# zmJackBoard.net
KiCad netlist of a schematic drawn in EAGLE
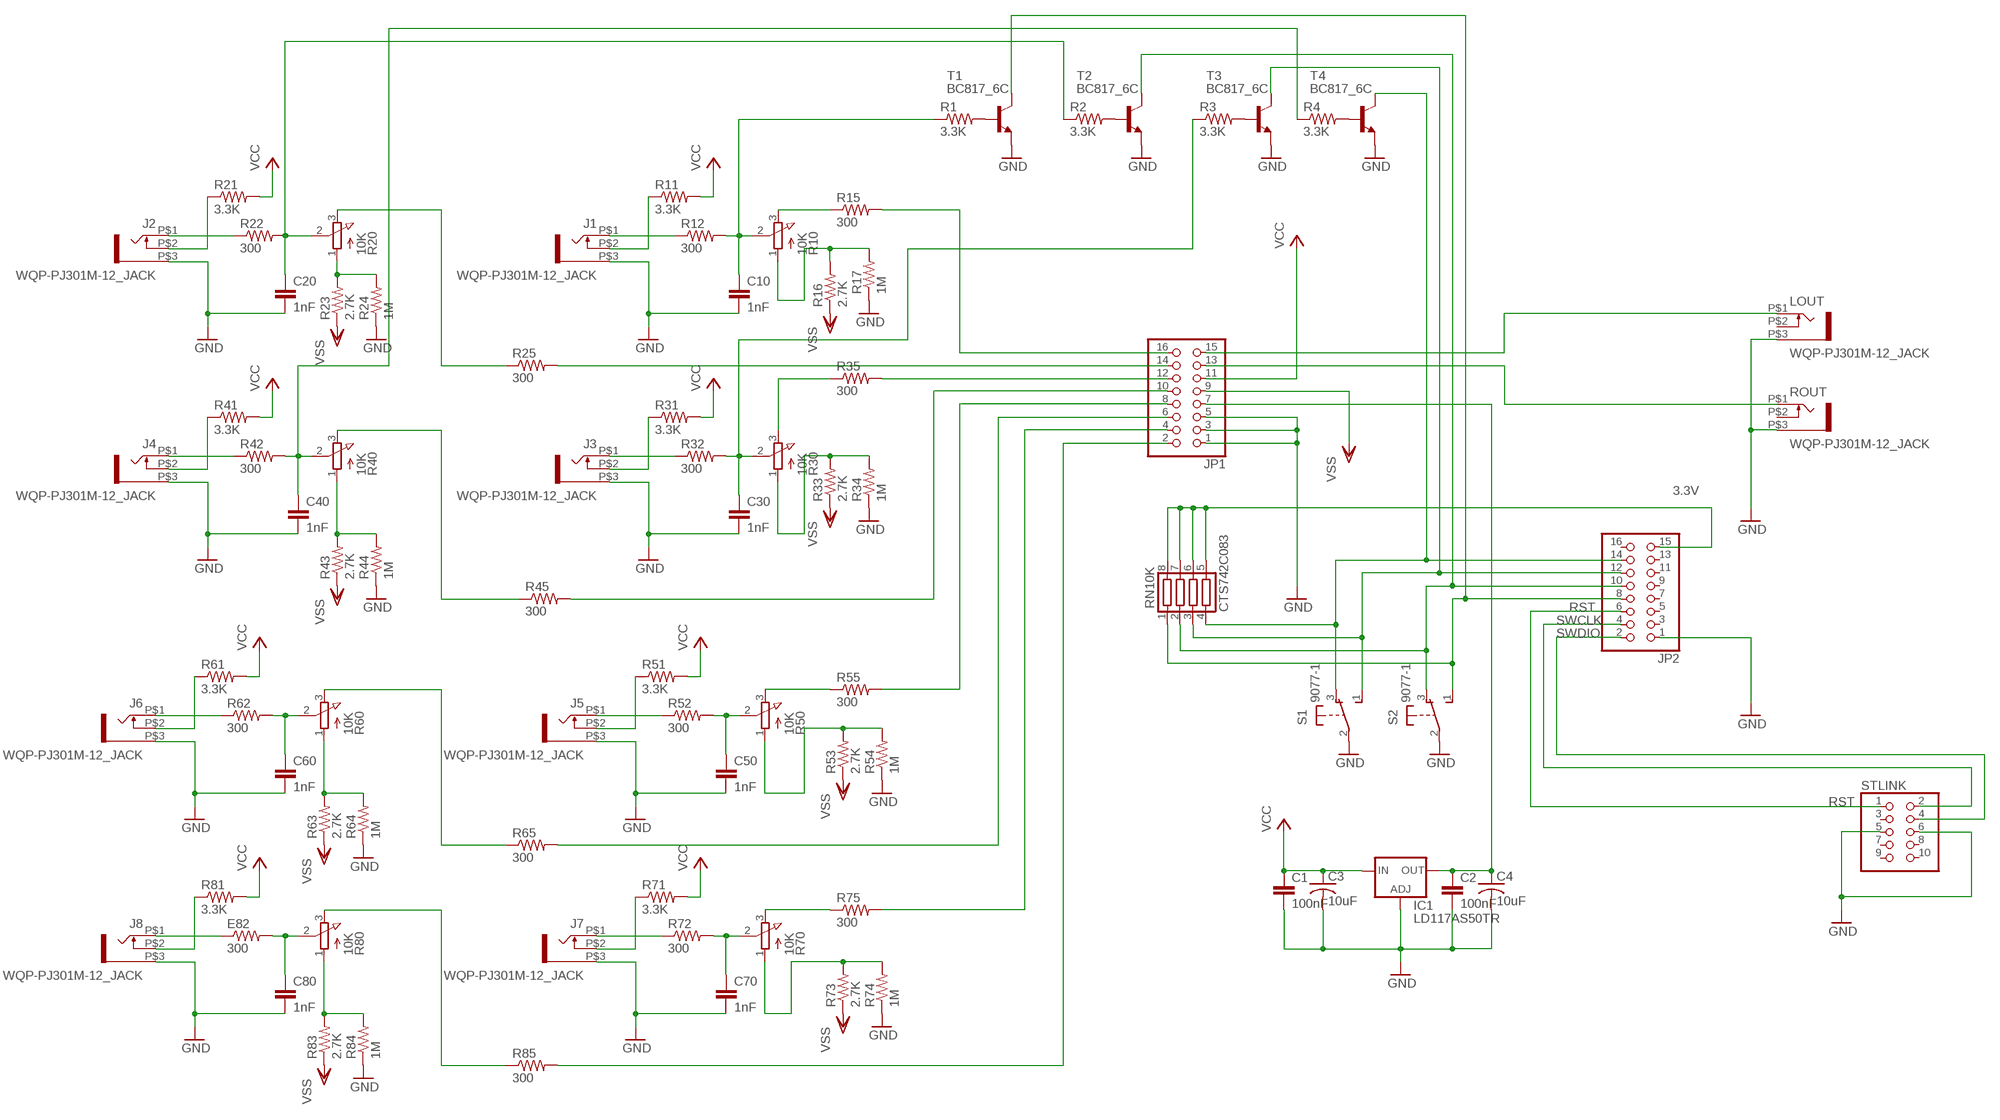
[diagram p0: schematic, sheet 1]

(export (version "E")
  (design (tool "Eeschema 10.0.6"))
  (components
    (comp (ref "C1")
      (value "100nF")
      (footprint "eagle-import:C0805")
      (libsource (lib "eagle-import") (part "C-EUC0805"))
    )
    (comp (ref "C2")
      (value "100nF")
      (footprint "eagle-import:C0805")
      (libsource (lib "eagle-import") (part "C-EUC0805"))
    )
    (comp (ref "C3")
      (value "10uF")
      (footprint "eagle-import:C1206")
      (libsource (lib "eagle-import") (part "C-USC1206"))
    )
    (comp (ref "C4")
      (value "10uF")
      (footprint "eagle-import:C1206")
      (libsource (lib "eagle-import") (part "C-USC1206"))
    )
    (comp (ref "C10")
      (value "1nF")
      (footprint "eagle-import:C0805")
      (libsource (lib "eagle-import") (part "C-EUC0805"))
    )
    (comp (ref "C20")
      (value "1nF")
      (footprint "eagle-import:C0805")
      (libsource (lib "eagle-import") (part "C-EUC0805"))
    )
    (comp (ref "C30")
      (value "1nF")
      (footprint "eagle-import:C0805")
      (libsource (lib "eagle-import") (part "C-EUC0805"))
    )
    (comp (ref "C40")
      (value "1nF")
      (footprint "eagle-import:C0805")
      (libsource (lib "eagle-import") (part "C-EUC0805"))
    )
    (comp (ref "C50")
      (value "1nF")
      (footprint "eagle-import:C0805")
      (libsource (lib "eagle-import") (part "C-EUC0805"))
    )
    (comp (ref "C60")
      (value "1nF")
      (footprint "eagle-import:C0805")
      (libsource (lib "eagle-import") (part "C-EUC0805"))
    )
    (comp (ref "C70")
      (value "1nF")
      (footprint "eagle-import:C0805")
      (libsource (lib "eagle-import") (part "C-EUC0805"))
    )
    (comp (ref "C80")
      (value "1nF")
      (footprint "eagle-import:C0805")
      (libsource (lib "eagle-import") (part "C-EUC0805"))
    )
    (comp (ref "E82")
      (value "300")
      (footprint "eagle-import:M0805")
      (libsource (lib "eagle-import") (part "R-US_M0805"))
    )
    (comp (ref "IC1")
      (value "LD117AS50TR")
      (footprint "eagle-import:SOT223")
      (libsource (lib "eagle-import") (part "LD117A?S50TR"))
    )
    (comp (ref "J1")
      (value "WQP-PJ301M-12_JACK")
      (footprint "eagle-import:WQP-PJ301M-12_JACK")
      (libsource (lib "eagle-import") (part "WQP-PJ301M-12_JACK"))
    )
    (comp (ref "J2")
      (value "WQP-PJ301M-12_JACK")
      (footprint "eagle-import:WQP-PJ301M-12_JACK")
      (libsource (lib "eagle-import") (part "WQP-PJ301M-12_JACK"))
    )
    (comp (ref "J3")
      (value "WQP-PJ301M-12_JACK")
      (footprint "eagle-import:WQP-PJ301M-12_JACK")
      (libsource (lib "eagle-import") (part "WQP-PJ301M-12_JACK"))
    )
    (comp (ref "J4")
      (value "WQP-PJ301M-12_JACK")
      (footprint "eagle-import:WQP-PJ301M-12_JACK")
      (libsource (lib "eagle-import") (part "WQP-PJ301M-12_JACK"))
    )
    (comp (ref "J5")
      (value "WQP-PJ301M-12_JACK")
      (footprint "eagle-import:WQP-PJ301M-12_JACK")
      (libsource (lib "eagle-import") (part "WQP-PJ301M-12_JACK"))
    )
    (comp (ref "J6")
      (value "WQP-PJ301M-12_JACK")
      (footprint "eagle-import:WQP-PJ301M-12_JACK")
      (libsource (lib "eagle-import") (part "WQP-PJ301M-12_JACK"))
    )
    (comp (ref "J7")
      (value "WQP-PJ301M-12_JACK")
      (footprint "eagle-import:WQP-PJ301M-12_JACK")
      (libsource (lib "eagle-import") (part "WQP-PJ301M-12_JACK"))
    )
    (comp (ref "J8")
      (value "WQP-PJ301M-12_JACK")
      (footprint "eagle-import:WQP-PJ301M-12_JACK")
      (libsource (lib "eagle-import") (part "WQP-PJ301M-12_JACK"))
    )
    (comp (ref "JP1")
      (value "PINHD-2X8")
      (footprint "eagle-import:2X08")
      (libsource (lib "eagle-import") (part "PINHD-2X8"))
    )
    (comp (ref "JP2")
      (value "PINHD-2X8")
      (footprint "eagle-import:2X08")
      (libsource (lib "eagle-import") (part "PINHD-2X8"))
    )
    (comp (ref "LOUT")
      (value "WQP-PJ301M-12_JACK")
      (footprint "eagle-import:WQP-PJ301M-12_JACK")
      (libsource (lib "eagle-import") (part "WQP-PJ301M-12_JACK"))
    )
    (comp (ref "R1")
      (value "3.3K")
      (footprint "eagle-import:M0805")
      (libsource (lib "eagle-import") (part "R-US_M0805"))
    )
    (comp (ref "R2")
      (value "3.3K")
      (footprint "eagle-import:M0805")
      (libsource (lib "eagle-import") (part "R-US_M0805"))
    )
    (comp (ref "R3")
      (value "3.3K")
      (footprint "eagle-import:M0805")
      (libsource (lib "eagle-import") (part "R-US_M0805"))
    )
    (comp (ref "R4")
      (value "3.3K")
      (footprint "eagle-import:M0805")
      (libsource (lib "eagle-import") (part "R-US_M0805"))
    )
    (comp (ref "R10")
      (value "10K")
      (footprint "eagle-import:EVUFXL")
      (libsource (lib "eagle-import") (part "EVULF3"))
    )
    (comp (ref "R11")
      (value "3.3K")
      (footprint "eagle-import:M0805")
      (libsource (lib "eagle-import") (part "R-US_M0805"))
    )
    (comp (ref "R12")
      (value "300")
      (footprint "eagle-import:M0805")
      (libsource (lib "eagle-import") (part "R-US_M0805"))
    )
    (comp (ref "R15")
      (value "300")
      (footprint "eagle-import:M0805")
      (libsource (lib "eagle-import") (part "R-US_M0805"))
    )
    (comp (ref "R16")
      (value "2.7K")
      (footprint "eagle-import:M0805")
      (libsource (lib "eagle-import") (part "R-US_M0805"))
    )
    (comp (ref "R17")
      (value "1M")
      (footprint "eagle-import:M0805")
      (libsource (lib "eagle-import") (part "R-US_M0805"))
    )
    (comp (ref "R20")
      (value "10K")
      (footprint "eagle-import:EVUFXL")
      (libsource (lib "eagle-import") (part "EVULF3"))
    )
    (comp (ref "R21")
      (value "3.3K")
      (footprint "eagle-import:M0805")
      (libsource (lib "eagle-import") (part "R-US_M0805"))
    )
    (comp (ref "R22")
      (value "300")
      (footprint "eagle-import:M0805")
      (libsource (lib "eagle-import") (part "R-US_M0805"))
    )
    (comp (ref "R23")
      (value "2.7K")
      (footprint "eagle-import:M0805")
      (libsource (lib "eagle-import") (part "R-US_M0805"))
    )
    (comp (ref "R24")
      (value "1M")
      (footprint "eagle-import:M0805")
      (libsource (lib "eagle-import") (part "R-US_M0805"))
    )
    (comp (ref "R25")
      (value "300")
      (footprint "eagle-import:M0805")
      (libsource (lib "eagle-import") (part "R-US_M0805"))
    )
    (comp (ref "R30")
      (value "10K")
      (footprint "eagle-import:EVUFXL")
      (libsource (lib "eagle-import") (part "EVULF3"))
    )
    (comp (ref "R31")
      (value "3.3K")
      (footprint "eagle-import:M0805")
      (libsource (lib "eagle-import") (part "R-US_M0805"))
    )
    (comp (ref "R32")
      (value "300")
      (footprint "eagle-import:M0805")
      (libsource (lib "eagle-import") (part "R-US_M0805"))
    )
    (comp (ref "R33")
      (value "2.7K")
      (footprint "eagle-import:M0805")
      (libsource (lib "eagle-import") (part "R-US_M0805"))
    )
    (comp (ref "R34")
      (value "1M")
      (footprint "eagle-import:M0805")
      (libsource (lib "eagle-import") (part "R-US_M0805"))
    )
    (comp (ref "R35")
      (value "300")
      (footprint "eagle-import:M0805")
      (libsource (lib "eagle-import") (part "R-US_M0805"))
    )
    (comp (ref "R40")
      (value "10K")
      (footprint "eagle-import:EVUFXL")
      (libsource (lib "eagle-import") (part "EVULF3"))
    )
    (comp (ref "R41")
      (value "3.3K")
      (footprint "eagle-import:M0805")
      (libsource (lib "eagle-import") (part "R-US_M0805"))
    )
    (comp (ref "R42")
      (value "300")
      (footprint "eagle-import:M0805")
      (libsource (lib "eagle-import") (part "R-US_M0805"))
    )
    (comp (ref "R43")
      (value "2.7K")
      (footprint "eagle-import:M0805")
      (libsource (lib "eagle-import") (part "R-US_M0805"))
    )
    (comp (ref "R44")
      (value "1M")
      (footprint "eagle-import:M0805")
      (libsource (lib "eagle-import") (part "R-US_M0805"))
    )
    (comp (ref "R45")
      (value "300")
      (footprint "eagle-import:M0805")
      (libsource (lib "eagle-import") (part "R-US_M0805"))
    )
    (comp (ref "R50")
      (value "10K")
      (footprint "eagle-import:EVUFXL")
      (libsource (lib "eagle-import") (part "EVULF3"))
    )
    (comp (ref "R51")
      (value "3.3K")
      (footprint "eagle-import:M0805")
      (libsource (lib "eagle-import") (part "R-US_M0805"))
    )
    (comp (ref "R52")
      (value "300")
      (footprint "eagle-import:M0805")
      (libsource (lib "eagle-import") (part "R-US_M0805"))
    )
    (comp (ref "R53")
      (value "2.7K")
      (footprint "eagle-import:M0805")
      (libsource (lib "eagle-import") (part "R-US_M0805"))
    )
    (comp (ref "R54")
      (value "1M")
      (footprint "eagle-import:M0805")
      (libsource (lib "eagle-import") (part "R-US_M0805"))
    )
    (comp (ref "R55")
      (value "300")
      (footprint "eagle-import:M0805")
      (libsource (lib "eagle-import") (part "R-US_M0805"))
    )
    (comp (ref "R60")
      (value "10K")
      (footprint "eagle-import:EVUFXL")
      (libsource (lib "eagle-import") (part "EVULF3"))
    )
    (comp (ref "R61")
      (value "3.3K")
      (footprint "eagle-import:M0805")
      (libsource (lib "eagle-import") (part "R-US_M0805"))
    )
    (comp (ref "R62")
      (value "300")
      (footprint "eagle-import:M0805")
      (libsource (lib "eagle-import") (part "R-US_M0805"))
    )
    (comp (ref "R63")
      (value "2.7K")
      (footprint "eagle-import:M0805")
      (libsource (lib "eagle-import") (part "R-US_M0805"))
    )
    (comp (ref "R64")
      (value "1M")
      (footprint "eagle-import:M0805")
      (libsource (lib "eagle-import") (part "R-US_M0805"))
    )
    (comp (ref "R65")
      (value "300")
      (footprint "eagle-import:M0805")
      (libsource (lib "eagle-import") (part "R-US_M0805"))
    )
    (comp (ref "R70")
      (value "10K")
      (footprint "eagle-import:EVUFXL")
      (libsource (lib "eagle-import") (part "EVULF3"))
    )
    (comp (ref "R71")
      (value "3.3K")
      (footprint "eagle-import:M0805")
      (libsource (lib "eagle-import") (part "R-US_M0805"))
    )
    (comp (ref "R72")
      (value "300")
      (footprint "eagle-import:M0805")
      (libsource (lib "eagle-import") (part "R-US_M0805"))
    )
    (comp (ref "R73")
      (value "2.7K")
      (footprint "eagle-import:M0805")
      (libsource (lib "eagle-import") (part "R-US_M0805"))
    )
    (comp (ref "R74")
      (value "1M")
      (footprint "eagle-import:M0805")
      (libsource (lib "eagle-import") (part "R-US_M0805"))
    )
    (comp (ref "R75")
      (value "300")
      (footprint "eagle-import:M0805")
      (libsource (lib "eagle-import") (part "R-US_M0805"))
    )
    (comp (ref "R80")
      (value "10K")
      (footprint "eagle-import:EVUFXL")
      (libsource (lib "eagle-import") (part "EVULF3"))
    )
    (comp (ref "R81")
      (value "3.3K")
      (footprint "eagle-import:M0805")
      (libsource (lib "eagle-import") (part "R-US_M0805"))
    )
    (comp (ref "R83")
      (value "2.7K")
      (footprint "eagle-import:M0805")
      (libsource (lib "eagle-import") (part "R-US_M0805"))
    )
    (comp (ref "R84")
      (value "1M")
      (footprint "eagle-import:M0805")
      (libsource (lib "eagle-import") (part "R-US_M0805"))
    )
    (comp (ref "R85")
      (value "300")
      (footprint "eagle-import:M0805")
      (libsource (lib "eagle-import") (part "R-US_M0805"))
    )
    (comp (ref "RN10K")
      (value "CTS742C083")
      (footprint "eagle-import:CTS742C083")
      (libsource (lib "eagle-import") (part "CTS742C083"))
    )
    (comp (ref "ROUT")
      (value "WQP-PJ301M-12_JACK")
      (footprint "eagle-import:WQP-PJ301M-12_JACK")
      (libsource (lib "eagle-import") (part "WQP-PJ301M-12_JACK"))
    )
    (comp (ref "S1")
      (value "9077-1")
      (footprint "eagle-import:9077-1")
      (libsource (lib "eagle-import") (part "9077-1"))
    )
    (comp (ref "S2")
      (value "9077-1")
      (footprint "eagle-import:9077-1")
      (libsource (lib "eagle-import") (part "9077-1"))
    )
    (comp (ref "STLINK")
      (value "PINHD-2X5")
      (footprint "eagle-import:2X05")
      (libsource (lib "eagle-import") (part "PINHD-2X5"))
    )
    (comp (ref "T1")
      (value "BC817_6C")
      (footprint "eagle-import:SOT23-EBC")
      (libsource (lib "eagle-import") (part "-NPN-SOT23-EBC"))
    )
    (comp (ref "T2")
      (value "BC817_6C")
      (footprint "eagle-import:SOT23-EBC")
      (libsource (lib "eagle-import") (part "-NPN-SOT23-EBC"))
    )
    (comp (ref "T3")
      (value "BC817_6C")
      (footprint "eagle-import:SOT23-EBC")
      (libsource (lib "eagle-import") (part "-NPN-SOT23-EBC"))
    )
    (comp (ref "T4")
      (value "BC817_6C")
      (footprint "eagle-import:SOT23-EBC")
      (libsource (lib "eagle-import") (part "-NPN-SOT23-EBC"))
    )
  )
  (nets
    (net (code "1") (name "/3.3V") (class "Default")
      (node (ref "JP2") (pin "15") (pinfunction "15_15") (pintype "passive"))
      (node (ref "RN10K") (pin "5") (pinfunction "5_5") (pintype "passive"))
      (node (ref "RN10K") (pin "6") (pinfunction "6_6") (pintype "passive"))
      (node (ref "RN10K") (pin "7") (pinfunction "7_7") (pintype "passive"))
      (node (ref "RN10K") (pin "8") (pinfunction "8_8") (pintype "passive"))
    )
    (net (code "2") (name "/RST") (class "Default")
      (node (ref "JP2") (pin "6") (pinfunction "6_6") (pintype "passive"))
      (node (ref "STLINK") (pin "1") (pinfunction "1_1") (pintype "passive"))
    )
    (net (code "3") (name "/SWCLK") (class "Default")
      (node (ref "JP2") (pin "4") (pinfunction "4_4") (pintype "passive"))
      (node (ref "STLINK") (pin "2") (pinfunction "2_2") (pintype "passive"))
    )
    (net (code "4") (name "/SWDIO") (class "Default")
      (node (ref "JP2") (pin "2") (pinfunction "2_2") (pintype "passive"))
      (node (ref "STLINK") (pin "4") (pinfunction "4_4") (pintype "passive"))
    )
    (net (code "5") (name "GND") (class "Default")
      (node (ref "C1") (pin "2") (pinfunction "2_2") (pintype "passive"))
      (node (ref "C10") (pin "2") (pinfunction "2_2") (pintype "passive"))
      (node (ref "C2") (pin "2") (pinfunction "2_2") (pintype "passive"))
      (node (ref "C20") (pin "2") (pinfunction "2_2") (pintype "passive"))
      (node (ref "C3") (pin "2") (pinfunction "2_2") (pintype "passive"))
      (node (ref "C30") (pin "2") (pinfunction "2_2") (pintype "passive"))
      (node (ref "C4") (pin "2") (pinfunction "2_2") (pintype "passive"))
      (node (ref "C40") (pin "2") (pinfunction "2_2") (pintype "passive"))
      (node (ref "C50") (pin "2") (pinfunction "2_2") (pintype "passive"))
      (node (ref "C60") (pin "2") (pinfunction "2_2") (pintype "passive"))
      (node (ref "C70") (pin "2") (pinfunction "2_2") (pintype "passive"))
      (node (ref "C80") (pin "2") (pinfunction "2_2") (pintype "passive"))
      (node (ref "IC1") (pin "1") (pinfunction "ADJ_1") (pintype "input"))
      (node (ref "J1") (pin "P$3") (pinfunction "1_P$3") (pintype "passive"))
      (node (ref "J2") (pin "P$3") (pinfunction "1_P$3") (pintype "passive"))
      (node (ref "J3") (pin "P$3") (pinfunction "1_P$3") (pintype "passive"))
      (node (ref "J4") (pin "P$3") (pinfunction "1_P$3") (pintype "passive"))
      (node (ref "J5") (pin "P$3") (pinfunction "1_P$3") (pintype "passive"))
      (node (ref "J6") (pin "P$3") (pinfunction "1_P$3") (pintype "passive"))
      (node (ref "J7") (pin "P$3") (pinfunction "1_P$3") (pintype "passive"))
      (node (ref "J8") (pin "P$3") (pinfunction "1_P$3") (pintype "passive"))
      (node (ref "JP1") (pin "1") (pinfunction "1_1") (pintype "passive"))
      (node (ref "JP1") (pin "3") (pinfunction "3_3") (pintype "passive"))
      (node (ref "JP1") (pin "5") (pinfunction "5_5") (pintype "passive"))
      (node (ref "JP2") (pin "1") (pinfunction "1_1") (pintype "passive"))
      (node (ref "LOUT") (pin "P$3") (pinfunction "1_P$3") (pintype "passive"))
      (node (ref "R17") (pin "1") (pinfunction "1_1") (pintype "passive"))
      (node (ref "R24") (pin "1") (pinfunction "1_1") (pintype "passive"))
      (node (ref "R34") (pin "1") (pinfunction "1_1") (pintype "passive"))
      (node (ref "R44") (pin "1") (pinfunction "1_1") (pintype "passive"))
      (node (ref "R54") (pin "1") (pinfunction "1_1") (pintype "passive"))
      (node (ref "R64") (pin "1") (pinfunction "1_1") (pintype "passive"))
      (node (ref "R74") (pin "1") (pinfunction "1_1") (pintype "passive"))
      (node (ref "R84") (pin "1") (pinfunction "1_1") (pintype "passive"))
      (node (ref "ROUT") (pin "P$3") (pinfunction "1_P$3") (pintype "passive"))
      (node (ref "S1") (pin "2") (pinfunction "P_2") (pintype "passive"))
      (node (ref "S2") (pin "2") (pinfunction "P_2") (pintype "passive"))
      (node (ref "STLINK") (pin "5") (pinfunction "5_5") (pintype "passive"))
      (node (ref "STLINK") (pin "6") (pinfunction "6_6") (pintype "passive"))
      (node (ref "T1") (pin "E") (pinfunction "E_E") (pintype "passive"))
      (node (ref "T2") (pin "E") (pinfunction "E_E") (pintype "passive"))
      (node (ref "T3") (pin "E") (pinfunction "E_E") (pintype "passive"))
      (node (ref "T4") (pin "E") (pinfunction "E_E") (pintype "passive"))
    )
    (net (code "6") (name "Net-(IC1-OUT)") (class "Default")
      (node (ref "C2") (pin "1") (pinfunction "1_1") (pintype "passive"))
      (node (ref "C4") (pin "1") (pinfunction "1_1") (pintype "passive"))
      (node (ref "IC1") (pin "4") (pinfunction "OUT_4") (pintype "passive"))
      (node (ref "JP1") (pin "7") (pinfunction "7_7") (pintype "passive"))
    )
    (net (code "7") (name "Net-(J1-2)") (class "Default")
      (node (ref "J1") (pin "P$1") (pinfunction "2_P$1") (pintype "passive"))
      (node (ref "R12") (pin "1") (pinfunction "1_1") (pintype "passive"))
    )
    (net (code "8") (name "Net-(J1-3)") (class "Default")
      (node (ref "J1") (pin "P$2") (pinfunction "3_P$2") (pintype "passive"))
      (node (ref "R11") (pin "1") (pinfunction "1_1") (pintype "passive"))
    )
    (net (code "9") (name "Net-(J2-2)") (class "Default")
      (node (ref "J2") (pin "P$1") (pinfunction "2_P$1") (pintype "passive"))
      (node (ref "R22") (pin "1") (pinfunction "1_1") (pintype "passive"))
    )
    (net (code "10") (name "Net-(J2-3)") (class "Default")
      (node (ref "J2") (pin "P$2") (pinfunction "3_P$2") (pintype "passive"))
      (node (ref "R21") (pin "1") (pinfunction "1_1") (pintype "passive"))
    )
    (net (code "11") (name "Net-(J3-2)") (class "Default")
      (node (ref "J3") (pin "P$1") (pinfunction "2_P$1") (pintype "passive"))
      (node (ref "R32") (pin "1") (pinfunction "1_1") (pintype "passive"))
    )
    (net (code "12") (name "Net-(J3-3)") (class "Default")
      (node (ref "J3") (pin "P$2") (pinfunction "3_P$2") (pintype "passive"))
      (node (ref "R31") (pin "1") (pinfunction "1_1") (pintype "passive"))
    )
    (net (code "13") (name "Net-(J4-2)") (class "Default")
      (node (ref "J4") (pin "P$1") (pinfunction "2_P$1") (pintype "passive"))
      (node (ref "R42") (pin "1") (pinfunction "1_1") (pintype "passive"))
    )
    (net (code "14") (name "Net-(J4-3)") (class "Default")
      (node (ref "J4") (pin "P$2") (pinfunction "3_P$2") (pintype "passive"))
      (node (ref "R41") (pin "1") (pinfunction "1_1") (pintype "passive"))
    )
    (net (code "15") (name "Net-(J5-2)") (class "Default")
      (node (ref "J5") (pin "P$1") (pinfunction "2_P$1") (pintype "passive"))
      (node (ref "R52") (pin "1") (pinfunction "1_1") (pintype "passive"))
    )
    (net (code "16") (name "Net-(J5-3)") (class "Default")
      (node (ref "J5") (pin "P$2") (pinfunction "3_P$2") (pintype "passive"))
      (node (ref "R51") (pin "1") (pinfunction "1_1") (pintype "passive"))
    )
    (net (code "17") (name "Net-(J6-2)") (class "Default")
      (node (ref "J6") (pin "P$1") (pinfunction "2_P$1") (pintype "passive"))
      (node (ref "R62") (pin "1") (pinfunction "1_1") (pintype "passive"))
    )
    (net (code "18") (name "Net-(J6-3)") (class "Default")
      (node (ref "J6") (pin "P$2") (pinfunction "3_P$2") (pintype "passive"))
      (node (ref "R61") (pin "1") (pinfunction "1_1") (pintype "passive"))
    )
    (net (code "19") (name "Net-(J7-2)") (class "Default")
      (node (ref "J7") (pin "P$1") (pinfunction "2_P$1") (pintype "passive"))
      (node (ref "R72") (pin "1") (pinfunction "1_1") (pintype "passive"))
    )
    (net (code "20") (name "Net-(J7-3)") (class "Default")
      (node (ref "J7") (pin "P$2") (pinfunction "3_P$2") (pintype "passive"))
      (node (ref "R71") (pin "1") (pinfunction "1_1") (pintype "passive"))
    )
    (net (code "21") (name "Net-(J8-2)") (class "Default")
      (node (ref "E82") (pin "1") (pinfunction "1_1") (pintype "passive"))
      (node (ref "J8") (pin "P$1") (pinfunction "2_P$1") (pintype "passive"))
    )
    (net (code "22") (name "Net-(J8-3)") (class "Default")
      (node (ref "J8") (pin "P$2") (pinfunction "3_P$2") (pintype "passive"))
      (node (ref "R81") (pin "1") (pinfunction "1_1") (pintype "passive"))
    )
    (net (code "23") (name "Net-(JP1-Pad2)") (class "Default")
      (node (ref "JP1") (pin "2") (pinfunction "2_2") (pintype "passive"))
      (node (ref "R85") (pin "2") (pinfunction "2_2") (pintype "passive"))
    )
    (net (code "24") (name "Net-(JP1-Pad4)") (class "Default")
      (node (ref "JP1") (pin "4") (pinfunction "4_4") (pintype "passive"))
      (node (ref "R75") (pin "2") (pinfunction "2_2") (pintype "passive"))
    )
    (net (code "25") (name "Net-(JP1-Pad6)") (class "Default")
      (node (ref "JP1") (pin "6") (pinfunction "6_6") (pintype "passive"))
      (node (ref "R65") (pin "2") (pinfunction "2_2") (pintype "passive"))
    )
    (net (code "26") (name "Net-(JP1-Pad8)") (class "Default")
      (node (ref "JP1") (pin "8") (pinfunction "8_8") (pintype "passive"))
      (node (ref "R55") (pin "2") (pinfunction "2_2") (pintype "passive"))
    )
    (net (code "27") (name "Net-(JP1-Pad10)") (class "Default")
      (node (ref "JP1") (pin "10") (pinfunction "10_10") (pintype "passive"))
      (node (ref "R45") (pin "2") (pinfunction "2_2") (pintype "passive"))
    )
    (net (code "28") (name "Net-(JP1-Pad12)") (class "Default")
      (node (ref "JP1") (pin "12") (pinfunction "12_12") (pintype "passive"))
      (node (ref "R35") (pin "2") (pinfunction "2_2") (pintype "passive"))
    )
    (net (code "29") (name "Net-(JP1-Pad14)") (class "Default")
      (node (ref "JP1") (pin "14") (pinfunction "14_14") (pintype "passive"))
      (node (ref "R25") (pin "2") (pinfunction "2_2") (pintype "passive"))
    )
    (net (code "30") (name "Net-(JP1-Pad16)") (class "Default")
      (node (ref "JP1") (pin "16") (pinfunction "16_16") (pintype "passive"))
      (node (ref "R15") (pin "2") (pinfunction "2_2") (pintype "passive"))
    )
    (net (code "31") (name "Net-(LOUT-2)") (class "Default")
      (node (ref "JP1") (pin "15") (pinfunction "15_15") (pintype "passive"))
      (node (ref "LOUT") (pin "P$1") (pinfunction "2_P$1") (pintype "passive"))
    )
    (net (code "32") (name "Net-(R1-Pad2)") (class "Default")
      (node (ref "R1") (pin "2") (pinfunction "2_2") (pintype "passive"))
      (node (ref "T1") (pin "B") (pinfunction "B_B") (pintype "passive"))
    )
    (net (code "33") (name "Net-(R2-Pad2)") (class "Default")
      (node (ref "R2") (pin "2") (pinfunction "2_2") (pintype "passive"))
      (node (ref "T2") (pin "B") (pinfunction "B_B") (pintype "passive"))
    )
    (net (code "34") (name "Net-(R3-Pad2)") (class "Default")
      (node (ref "R3") (pin "2") (pinfunction "2_2") (pintype "passive"))
      (node (ref "T3") (pin "B") (pinfunction "B_B") (pintype "passive"))
    )
    (net (code "35") (name "Net-(R4-Pad2)") (class "Default")
      (node (ref "R4") (pin "2") (pinfunction "2_2") (pintype "passive"))
      (node (ref "T4") (pin "B") (pinfunction "B_B") (pintype "passive"))
    )
    (net (code "36") (name "Net-(R10-A)") (class "Default")
      (node (ref "R10") (pin "1") (pinfunction "A_1") (pintype "passive"))
      (node (ref "R16") (pin "2") (pinfunction "2_2") (pintype "passive"))
      (node (ref "R17") (pin "2") (pinfunction "2_2") (pintype "passive"))
    )
    (net (code "37") (name "Net-(R10-E)") (class "Default")
      (node (ref "R10") (pin "3") (pinfunction "E_3") (pintype "passive"))
      (node (ref "R15") (pin "1") (pinfunction "1_1") (pintype "passive"))
    )
    (net (code "38") (name "Net-(R10-S)") (class "Default")
      (node (ref "C10") (pin "1") (pinfunction "1_1") (pintype "passive"))
      (node (ref "R1") (pin "1") (pinfunction "1_1") (pintype "passive"))
      (node (ref "R10") (pin "2") (pinfunction "S_2") (pintype "passive"))
      (node (ref "R12") (pin "2") (pinfunction "2_2") (pintype "passive"))
    )
    (net (code "39") (name "Net-(R20-A)") (class "Default")
      (node (ref "R20") (pin "1") (pinfunction "A_1") (pintype "passive"))
      (node (ref "R23") (pin "2") (pinfunction "2_2") (pintype "passive"))
      (node (ref "R24") (pin "2") (pinfunction "2_2") (pintype "passive"))
    )
    (net (code "40") (name "Net-(R20-E)") (class "Default")
      (node (ref "R20") (pin "3") (pinfunction "E_3") (pintype "passive"))
      (node (ref "R25") (pin "1") (pinfunction "1_1") (pintype "passive"))
    )
    (net (code "41") (name "Net-(R20-S)") (class "Default")
      (node (ref "C20") (pin "1") (pinfunction "1_1") (pintype "passive"))
      (node (ref "R2") (pin "1") (pinfunction "1_1") (pintype "passive"))
      (node (ref "R20") (pin "2") (pinfunction "S_2") (pintype "passive"))
      (node (ref "R22") (pin "2") (pinfunction "2_2") (pintype "passive"))
    )
    (net (code "42") (name "Net-(R30-A)") (class "Default")
      (node (ref "R30") (pin "1") (pinfunction "A_1") (pintype "passive"))
      (node (ref "R33") (pin "2") (pinfunction "2_2") (pintype "passive"))
      (node (ref "R34") (pin "2") (pinfunction "2_2") (pintype "passive"))
    )
    (net (code "43") (name "Net-(R30-E)") (class "Default")
      (node (ref "R30") (pin "3") (pinfunction "E_3") (pintype "passive"))
      (node (ref "R35") (pin "1") (pinfunction "1_1") (pintype "passive"))
    )
    (net (code "44") (name "Net-(R30-S)") (class "Default")
      (node (ref "C30") (pin "1") (pinfunction "1_1") (pintype "passive"))
      (node (ref "R3") (pin "1") (pinfunction "1_1") (pintype "passive"))
      (node (ref "R30") (pin "2") (pinfunction "S_2") (pintype "passive"))
      (node (ref "R32") (pin "2") (pinfunction "2_2") (pintype "passive"))
    )
    (net (code "45") (name "Net-(R40-A)") (class "Default")
      (node (ref "R40") (pin "1") (pinfunction "A_1") (pintype "passive"))
      (node (ref "R43") (pin "2") (pinfunction "2_2") (pintype "passive"))
      (node (ref "R44") (pin "2") (pinfunction "2_2") (pintype "passive"))
    )
    (net (code "46") (name "Net-(R40-E)") (class "Default")
      (node (ref "R40") (pin "3") (pinfunction "E_3") (pintype "passive"))
      (node (ref "R45") (pin "1") (pinfunction "1_1") (pintype "passive"))
    )
    (net (code "47") (name "Net-(R40-S)") (class "Default")
      (node (ref "C40") (pin "1") (pinfunction "1_1") (pintype "passive"))
      (node (ref "R4") (pin "1") (pinfunction "1_1") (pintype "passive"))
      (node (ref "R40") (pin "2") (pinfunction "S_2") (pintype "passive"))
      (node (ref "R42") (pin "2") (pinfunction "2_2") (pintype "passive"))
    )
    (net (code "48") (name "Net-(R50-A)") (class "Default")
      (node (ref "R50") (pin "1") (pinfunction "A_1") (pintype "passive"))
      (node (ref "R53") (pin "2") (pinfunction "2_2") (pintype "passive"))
      (node (ref "R54") (pin "2") (pinfunction "2_2") (pintype "passive"))
    )
    (net (code "49") (name "Net-(R50-E)") (class "Default")
      (node (ref "R50") (pin "3") (pinfunction "E_3") (pintype "passive"))
      (node (ref "R55") (pin "1") (pinfunction "1_1") (pintype "passive"))
    )
    (net (code "50") (name "Net-(R50-S)") (class "Default")
      (node (ref "C50") (pin "1") (pinfunction "1_1") (pintype "passive"))
      (node (ref "R50") (pin "2") (pinfunction "S_2") (pintype "passive"))
      (node (ref "R52") (pin "2") (pinfunction "2_2") (pintype "passive"))
    )
    (net (code "51") (name "Net-(R60-A)") (class "Default")
      (node (ref "R60") (pin "1") (pinfunction "A_1") (pintype "passive"))
      (node (ref "R63") (pin "2") (pinfunction "2_2") (pintype "passive"))
      (node (ref "R64") (pin "2") (pinfunction "2_2") (pintype "passive"))
    )
    (net (code "52") (name "Net-(R60-E)") (class "Default")
      (node (ref "R60") (pin "3") (pinfunction "E_3") (pintype "passive"))
      (node (ref "R65") (pin "1") (pinfunction "1_1") (pintype "passive"))
    )
    (net (code "53") (name "Net-(R60-S)") (class "Default")
      (node (ref "C60") (pin "1") (pinfunction "1_1") (pintype "passive"))
      (node (ref "R60") (pin "2") (pinfunction "S_2") (pintype "passive"))
      (node (ref "R62") (pin "2") (pinfunction "2_2") (pintype "passive"))
    )
    (net (code "54") (name "Net-(R70-A)") (class "Default")
      (node (ref "R70") (pin "1") (pinfunction "A_1") (pintype "passive"))
      (node (ref "R73") (pin "2") (pinfunction "2_2") (pintype "passive"))
      (node (ref "R74") (pin "2") (pinfunction "2_2") (pintype "passive"))
    )
    (net (code "55") (name "Net-(R70-E)") (class "Default")
      (node (ref "R70") (pin "3") (pinfunction "E_3") (pintype "passive"))
      (node (ref "R75") (pin "1") (pinfunction "1_1") (pintype "passive"))
    )
    (net (code "56") (name "Net-(R70-S)") (class "Default")
      (node (ref "C70") (pin "1") (pinfunction "1_1") (pintype "passive"))
      (node (ref "R70") (pin "2") (pinfunction "S_2") (pintype "passive"))
      (node (ref "R72") (pin "2") (pinfunction "2_2") (pintype "passive"))
    )
    (net (code "57") (name "Net-(R80-A)") (class "Default")
      (node (ref "R80") (pin "1") (pinfunction "A_1") (pintype "passive"))
      (node (ref "R83") (pin "2") (pinfunction "2_2") (pintype "passive"))
      (node (ref "R84") (pin "2") (pinfunction "2_2") (pintype "passive"))
    )
    (net (code "58") (name "Net-(R80-E)") (class "Default")
      (node (ref "R80") (pin "3") (pinfunction "E_3") (pintype "passive"))
      (node (ref "R85") (pin "1") (pinfunction "1_1") (pintype "passive"))
    )
    (net (code "59") (name "Net-(R80-S)") (class "Default")
      (node (ref "C80") (pin "1") (pinfunction "1_1") (pintype "passive"))
      (node (ref "E82") (pin "2") (pinfunction "2_2") (pintype "passive"))
      (node (ref "R80") (pin "2") (pinfunction "S_2") (pintype "passive"))
    )
    (net (code "60") (name "Net-(ROUT-2)") (class "Default")
      (node (ref "JP1") (pin "13") (pinfunction "13_13") (pintype "passive"))
      (node (ref "ROUT") (pin "P$1") (pinfunction "2_P$1") (pintype "passive"))
    )
    (net (code "61") (name "Net-(S1-O)") (class "Default")
      (node (ref "JP2") (pin "14") (pinfunction "14_14") (pintype "passive"))
      (node (ref "RN10K") (pin "4") (pinfunction "4_4") (pintype "passive"))
      (node (ref "S1") (pin "3") (pinfunction "O_3") (pintype "passive"))
      (node (ref "T4") (pin "C") (pinfunction "C_C") (pintype "passive"))
    )
    (net (code "62") (name "Net-(S1-S)") (class "Default")
      (node (ref "JP2") (pin "12") (pinfunction "12_12") (pintype "passive"))
      (node (ref "RN10K") (pin "3") (pinfunction "3_3") (pintype "passive"))
      (node (ref "S1") (pin "1") (pinfunction "S_1") (pintype "passive"))
      (node (ref "T3") (pin "C") (pinfunction "C_C") (pintype "passive"))
    )
    (net (code "63") (name "Net-(S2-O)") (class "Default")
      (node (ref "JP2") (pin "10") (pinfunction "10_10") (pintype "passive"))
      (node (ref "RN10K") (pin "2") (pinfunction "2_2") (pintype "passive"))
      (node (ref "S2") (pin "3") (pinfunction "O_3") (pintype "passive"))
      (node (ref "T2") (pin "C") (pinfunction "C_C") (pintype "passive"))
    )
    (net (code "64") (name "Net-(S2-S)") (class "Default")
      (node (ref "JP2") (pin "8") (pinfunction "8_8") (pintype "passive"))
      (node (ref "RN10K") (pin "1") (pinfunction "1_1") (pintype "passive"))
      (node (ref "S2") (pin "1") (pinfunction "S_1") (pintype "passive"))
      (node (ref "T1") (pin "C") (pinfunction "C_C") (pintype "passive"))
    )
    (net (code "65") (name "VCC") (class "Default")
      (node (ref "C1") (pin "1") (pinfunction "1_1") (pintype "passive"))
      (node (ref "C3") (pin "1") (pinfunction "1_1") (pintype "passive"))
      (node (ref "IC1") (pin "3") (pinfunction "IN_3") (pintype "input"))
      (node (ref "JP1") (pin "11") (pinfunction "11_11") (pintype "passive"))
      (node (ref "R11") (pin "2") (pinfunction "2_2") (pintype "passive"))
      (node (ref "R21") (pin "2") (pinfunction "2_2") (pintype "passive"))
      (node (ref "R31") (pin "2") (pinfunction "2_2") (pintype "passive"))
      (node (ref "R41") (pin "2") (pinfunction "2_2") (pintype "passive"))
      (node (ref "R51") (pin "2") (pinfunction "2_2") (pintype "passive"))
      (node (ref "R61") (pin "2") (pinfunction "2_2") (pintype "passive"))
      (node (ref "R71") (pin "2") (pinfunction "2_2") (pintype "passive"))
      (node (ref "R81") (pin "2") (pinfunction "2_2") (pintype "passive"))
    )
    (net (code "66") (name "VSS") (class "Default")
      (node (ref "JP1") (pin "9") (pinfunction "9_9") (pintype "passive"))
      (node (ref "R16") (pin "1") (pinfunction "1_1") (pintype "passive"))
      (node (ref "R23") (pin "1") (pinfunction "1_1") (pintype "passive"))
      (node (ref "R33") (pin "1") (pinfunction "1_1") (pintype "passive"))
      (node (ref "R43") (pin "1") (pinfunction "1_1") (pintype "passive"))
      (node (ref "R53") (pin "1") (pinfunction "1_1") (pintype "passive"))
      (node (ref "R63") (pin "1") (pinfunction "1_1") (pintype "passive"))
      (node (ref "R73") (pin "1") (pinfunction "1_1") (pintype "passive"))
      (node (ref "R83") (pin "1") (pinfunction "1_1") (pintype "passive"))
    )
    (net (code "67") (name "unconnected-(JP2-Pad3)") (class "Default")
      (node (ref "JP2") (pin "3") (pinfunction "3_3") (pintype "passive"))
    )
    (net (code "68") (name "unconnected-(JP2-Pad5)") (class "Default")
      (node (ref "JP2") (pin "5") (pinfunction "5_5") (pintype "passive"))
    )
    (net (code "69") (name "unconnected-(JP2-Pad7)") (class "Default")
      (node (ref "JP2") (pin "7") (pinfunction "7_7") (pintype "passive"))
    )
    (net (code "70") (name "unconnected-(JP2-Pad9)") (class "Default")
      (node (ref "JP2") (pin "9") (pinfunction "9_9") (pintype "passive"))
    )
    (net (code "71") (name "unconnected-(JP2-Pad11)") (class "Default")
      (node (ref "JP2") (pin "11") (pinfunction "11_11") (pintype "passive"))
    )
    (net (code "72") (name "unconnected-(JP2-Pad13)") (class "Default")
      (node (ref "JP2") (pin "13") (pinfunction "13_13") (pintype "passive"))
    )
    (net (code "73") (name "unconnected-(JP2-Pad16)") (class "Default")
      (node (ref "JP2") (pin "16") (pinfunction "16_16") (pintype "passive"))
    )
    (net (code "74") (name "unconnected-(LOUT-3-PadP$2)") (class "Default")
      (node (ref "LOUT") (pin "P$2") (pinfunction "3_P$2") (pintype "passive"))
    )
    (net (code "75") (name "unconnected-(ROUT-3-PadP$2)") (class "Default")
      (node (ref "ROUT") (pin "P$2") (pinfunction "3_P$2") (pintype "passive"))
    )
    (net (code "76") (name "unconnected-(STLINK-Pad3)") (class "Default")
      (node (ref "STLINK") (pin "3") (pinfunction "3_3") (pintype "passive"))
    )
    (net (code "77") (name "unconnected-(STLINK-Pad7)") (class "Default")
      (node (ref "STLINK") (pin "7") (pinfunction "7_7") (pintype "passive"))
    )
    (net (code "78") (name "unconnected-(STLINK-Pad8)") (class "Default")
      (node (ref "STLINK") (pin "8") (pinfunction "8_8") (pintype "passive"))
    )
    (net (code "79") (name "unconnected-(STLINK-Pad9)") (class "Default")
      (node (ref "STLINK") (pin "9") (pinfunction "9_9") (pintype "passive"))
    )
    (net (code "80") (name "unconnected-(STLINK-Pad10)") (class "Default")
      (node (ref "STLINK") (pin "10") (pinfunction "10_10") (pintype "passive"))
    )
  )
)
